# Incubadora_huevos.net
KiCad netlist of a schematic drawn in EAGLE
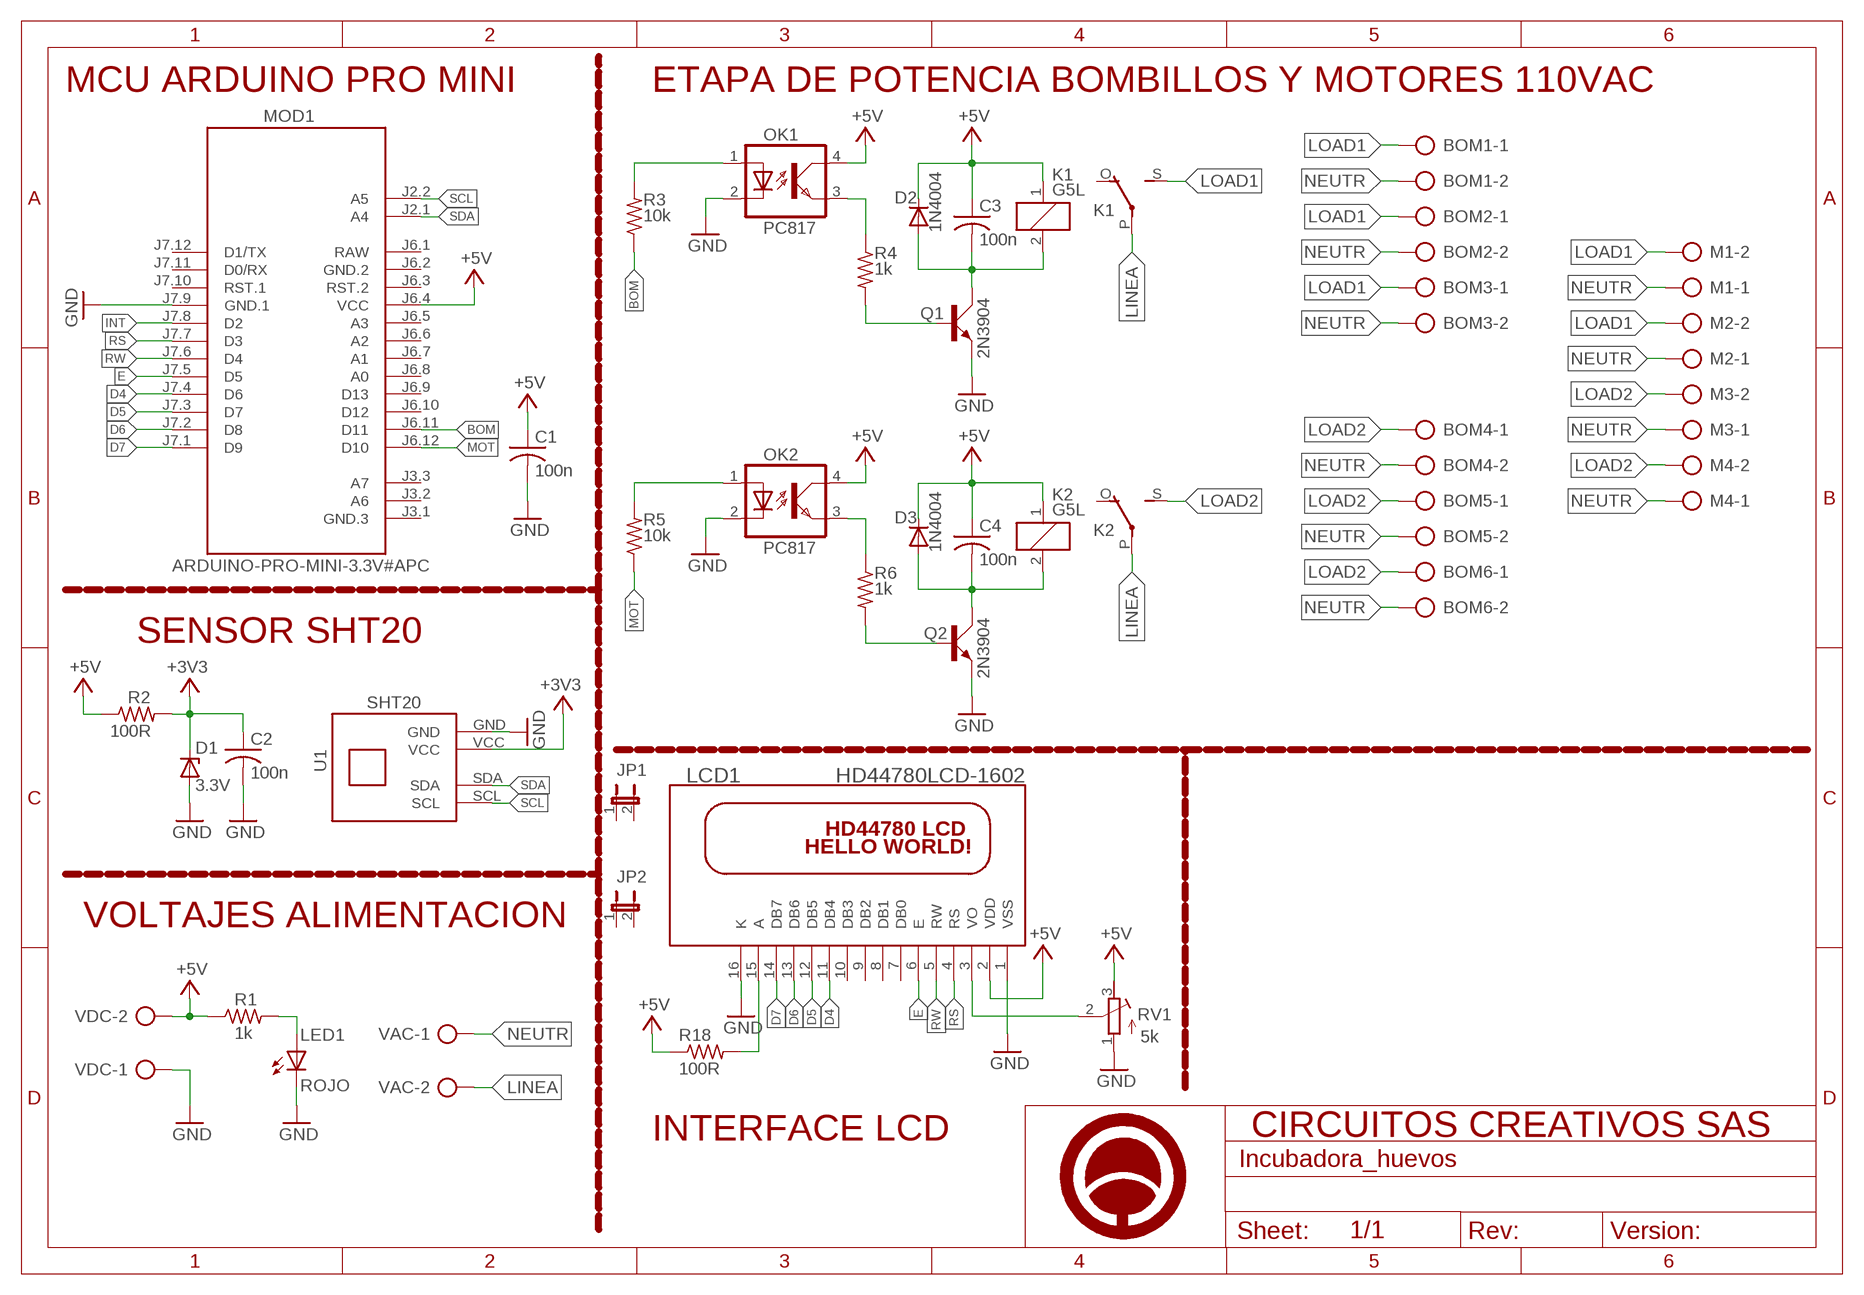
[diagram p0: schematic, sheet 1]

(export (version "E")
  (design (tool "Eeschema 10.0.6"))
  (components
    (comp (ref "BOM1")
      (value "AK500/2")
      (footprint "eagle-import:AK500_2")
      (libsource (lib "eagle-import") (part "AK500/2"))
    )
    (comp (ref "BOM2")
      (value "AK500/2")
      (footprint "eagle-import:AK500_2")
      (libsource (lib "eagle-import") (part "AK500/2"))
    )
    (comp (ref "BOM3")
      (value "AK500/2")
      (footprint "eagle-import:AK500_2")
      (libsource (lib "eagle-import") (part "AK500/2"))
    )
    (comp (ref "BOM4")
      (value "AK500/2")
      (footprint "eagle-import:AK500_2")
      (libsource (lib "eagle-import") (part "AK500/2"))
    )
    (comp (ref "BOM5")
      (value "AK500/2")
      (footprint "eagle-import:AK500_2")
      (libsource (lib "eagle-import") (part "AK500/2"))
    )
    (comp (ref "BOM6")
      (value "AK500/2")
      (footprint "eagle-import:AK500_2")
      (libsource (lib "eagle-import") (part "AK500/2"))
    )
    (comp (ref "C1")
      (value "100n")
      (footprint "eagle-import:C025-025X050")
      (libsource (lib "eagle-import") (part "C-US025-025X050"))
    )
    (comp (ref "C2")
      (value "100n")
      (footprint "eagle-import:C025-025X050")
      (libsource (lib "eagle-import") (part "C-US025-025X050"))
    )
    (comp (ref "C3")
      (value "100n")
      (footprint "eagle-import:C025-025X050")
      (libsource (lib "eagle-import") (part "C-US025-025X050"))
    )
    (comp (ref "C4")
      (value "100n")
      (footprint "eagle-import:C025-025X050")
      (libsource (lib "eagle-import") (part "C-US025-025X050"))
    )
    (comp (ref "D1")
      (value "3.3V")
      (footprint "eagle-import:DO41Z10")
      (libsource (lib "eagle-import") (part "ZENER-DIODEDO41Z10"))
    )
    (comp (ref "D2")
      (value "1N4004")
      (footprint "eagle-import:DO41-10")
      (libsource (lib "eagle-import") (part "1N4004"))
    )
    (comp (ref "D3")
      (value "1N4004")
      (footprint "eagle-import:DO41-10")
      (libsource (lib "eagle-import") (part "1N4004"))
    )
    (comp (ref "JP1")
      (value "JP1E")
      (footprint "eagle-import:JP1")
      (libsource (lib "eagle-import") (part "JP1E"))
    )
    (comp (ref "JP2")
      (value "JP1E")
      (footprint "eagle-import:JP1")
      (libsource (lib "eagle-import") (part "JP1E"))
    )
    (comp (ref "K1")
      (value "G5L")
      (footprint "eagle-import:G5LE")
      (libsource (lib "eagle-import") (part "G5L"))
    )
    (comp (ref "K2")
      (value "G5L")
      (footprint "eagle-import:G5LE")
      (libsource (lib "eagle-import") (part "G5L"))
    )
    (comp (ref "LCD1")
      (value "HD44780LCD-1602")
      (footprint "eagle-import:LCD1602")
      (libsource (lib "eagle-import") (part "HD44780LCD-1602"))
    )
    (comp (ref "LED1")
      (value "ROJO")
      (footprint "eagle-import:LED3MM")
      (libsource (lib "eagle-import") (part "LED3MM"))
    )
    (comp (ref "M1")
      (value "AK500/2")
      (footprint "eagle-import:AK500_2")
      (libsource (lib "eagle-import") (part "AK500/2"))
    )
    (comp (ref "M2")
      (value "AK500/2")
      (footprint "eagle-import:AK500_2")
      (libsource (lib "eagle-import") (part "AK500/2"))
    )
    (comp (ref "M3")
      (value "AK500/2")
      (footprint "eagle-import:AK500_2")
      (libsource (lib "eagle-import") (part "AK500/2"))
    )
    (comp (ref "M4")
      (value "AK500/2")
      (footprint "eagle-import:AK500_2")
      (libsource (lib "eagle-import") (part "AK500/2"))
    )
    (comp (ref "MOD1")
      (value "ARDUINO-PRO-MINI-3.3V#APC")
      (footprint "eagle-import:ARDUINO-PRO-MINI#APC")
      (libsource (lib "eagle-import") (part "ARDUINO-PRO-MINI-#APC3.3V"))
    )
    (comp (ref "OK1")
      (value "PC817")
      (footprint "eagle-import:DIL04")
      (fields (field (name "MPN") "PC817X4J000F"))
      (libsource (lib "eagle-import") (part "PC817"))
    )
    (comp (ref "OK2")
      (value "PC817")
      (footprint "eagle-import:DIL04")
      (fields (field (name "MPN") "PC817X4J000F"))
      (libsource (lib "eagle-import") (part "PC817"))
    )
    (comp (ref "Q1")
      (value "2N3904")
      (footprint "eagle-import:TO92D")
      (libsource (lib "eagle-import") (part "2N3904"))
    )
    (comp (ref "Q2")
      (value "2N3904")
      (footprint "eagle-import:TO92D")
      (libsource (lib "eagle-import") (part "2N3904"))
    )
    (comp (ref "R1")
      (value "1k")
      (footprint "eagle-import:0204_7")
      (libsource (lib "eagle-import") (part "R-US_0204/7"))
    )
    (comp (ref "R2")
      (value "100R")
      (footprint "eagle-import:0204_7")
      (libsource (lib "eagle-import") (part "R-US_0204/7"))
    )
    (comp (ref "R3")
      (value "10k")
      (footprint "eagle-import:0204_7")
      (libsource (lib "eagle-import") (part "R-US_0204/7"))
    )
    (comp (ref "R4")
      (value "1k")
      (footprint "eagle-import:0204_7")
      (libsource (lib "eagle-import") (part "R-US_0204/7"))
    )
    (comp (ref "R5")
      (value "10k")
      (footprint "eagle-import:0204_7")
      (libsource (lib "eagle-import") (part "R-US_0204/7"))
    )
    (comp (ref "R6")
      (value "1k")
      (footprint "eagle-import:0204_7")
      (libsource (lib "eagle-import") (part "R-US_0204/7"))
    )
    (comp (ref "R18")
      (value "100R")
      (footprint "eagle-import:0204_7")
      (libsource (lib "eagle-import") (part "R-US_0204/7"))
    )
    (comp (ref "RV1")
      (value "5k")
      (footprint "eagle-import:RTRIM3296W")
      (libsource (lib "eagle-import") (part "R-TRIMM3296W"))
    )
    (comp (ref "U$1")
      (value "A4_HORIZONTAL")
      (footprint "eagle-import:LOGO")
      (libsource (lib "eagle-import") (part "A4_HORIZONTAL"))
    )
    (comp (ref "U1")
      (value "SHT20")
      (footprint "eagle-import:SHT20")
      (libsource (lib "eagle-import") (part "SHT20"))
    )
    (comp (ref "VAC")
      (value "AK500/2")
      (footprint "eagle-import:AK500_2")
      (libsource (lib "eagle-import") (part "AK500/2"))
    )
    (comp (ref "VDC")
      (value "AK500/2")
      (footprint "eagle-import:AK500_2")
      (libsource (lib "eagle-import") (part "AK500/2"))
    )
  )
  (nets
    (net (code "1") (name "+3V3") (class "Default")
      (node (ref "C2") (pin "1") (pinfunction "1_1") (pintype "passive"))
      (node (ref "D1") (pin "C") (pinfunction "C_C") (pintype "passive"))
      (node (ref "R2") (pin "2") (pinfunction "2_2") (pintype "passive"))
      (node (ref "U1") (pin "VCC") (pinfunction "VCC_VCC") (pintype "power_in"))
    )
    (net (code "2") (name "+5V") (class "Default")
      (node (ref "C1") (pin "1") (pinfunction "1_1") (pintype "passive"))
      (node (ref "C3") (pin "1") (pinfunction "1_1") (pintype "passive"))
      (node (ref "C4") (pin "1") (pinfunction "1_1") (pintype "passive"))
      (node (ref "D2") (pin "C") (pinfunction "C_C") (pintype "passive"))
      (node (ref "D3") (pin "C") (pinfunction "C_C") (pintype "passive"))
      (node (ref "K1") (pin "1") (pinfunction "1_1") (pintype "passive"))
      (node (ref "K2") (pin "1") (pinfunction "1_1") (pintype "passive"))
      (node (ref "LCD1") (pin "2") (pinfunction "VDD_2") (pintype "power_in"))
      (node (ref "MOD1") (pin "J6.4") (pinfunction "VCC_J6.4") (pintype "power_in"))
      (node (ref "OK1") (pin "4") (pinfunction "COL_4") (pintype "passive"))
      (node (ref "OK2") (pin "4") (pinfunction "COL_4") (pintype "passive"))
      (node (ref "R1") (pin "1") (pinfunction "1_1") (pintype "passive"))
      (node (ref "R18") (pin "1") (pinfunction "1_1") (pintype "passive"))
      (node (ref "R2") (pin "1") (pinfunction "1_1") (pintype "passive"))
      (node (ref "RV1") (pin "3") (pinfunction "E_3") (pintype "passive"))
      (node (ref "VDC") (pin "2") (pinfunction "KL_2") (pintype "passive"))
    )
    (net (code "3") (name "/GND.2") (class "Default")
      (node (ref "MOD1") (pin "J6.2") (pinfunction "GND.2_J6.2") (pintype "power_in"))
    )
    (net (code "4") (name "/RAW") (class "Default")
      (node (ref "MOD1") (pin "J6.1") (pinfunction "RAW_J6.1") (pintype "power_in"))
    )
    (net (code "5") (name "BOM") (class "Default")
      (node (ref "MOD1") (pin "J6.11") (pinfunction "D11_J6.11") (pintype "bidirectional"))
      (node (ref "R3") (pin "1") (pinfunction "1_1") (pintype "passive"))
    )
    (net (code "6") (name "D4") (class "Default")
      (node (ref "LCD1") (pin "11") (pinfunction "DB4_11") (pintype "bidirectional"))
      (node (ref "MOD1") (pin "J7.4") (pinfunction "D6_J7.4") (pintype "bidirectional"))
    )
    (net (code "7") (name "D5") (class "Default")
      (node (ref "LCD1") (pin "12") (pinfunction "DB5_12") (pintype "bidirectional"))
      (node (ref "MOD1") (pin "J7.3") (pinfunction "D7_J7.3") (pintype "bidirectional"))
    )
    (net (code "8") (name "D6") (class "Default")
      (node (ref "LCD1") (pin "13") (pinfunction "DB6_13") (pintype "bidirectional"))
      (node (ref "MOD1") (pin "J7.2") (pinfunction "D8_J7.2") (pintype "bidirectional"))
    )
    (net (code "9") (name "D7") (class "Default")
      (node (ref "LCD1") (pin "14") (pinfunction "DB7_14") (pintype "bidirectional"))
      (node (ref "MOD1") (pin "J7.1") (pinfunction "D9_J7.1") (pintype "bidirectional"))
    )
    (net (code "10") (name "E") (class "Default")
      (node (ref "LCD1") (pin "6") (pinfunction "E_6") (pintype "input"))
      (node (ref "MOD1") (pin "J7.5") (pinfunction "D5_J7.5") (pintype "bidirectional"))
    )
    (net (code "11") (name "GND") (class "Default")
      (node (ref "C1") (pin "2") (pinfunction "2_2") (pintype "passive"))
      (node (ref "C2") (pin "2") (pinfunction "2_2") (pintype "passive"))
      (node (ref "D1") (pin "A") (pinfunction "A_A") (pintype "passive"))
      (node (ref "LCD1") (pin "1") (pinfunction "VSS_1") (pintype "power_in"))
      (node (ref "LCD1") (pin "16") (pinfunction "K_16") (pintype "input"))
      (node (ref "LED1") (pin "K") (pinfunction "C_K") (pintype "passive"))
      (node (ref "MOD1") (pin "J7.9") (pinfunction "GND.1_J7.9") (pintype "power_in"))
      (node (ref "OK1") (pin "2") (pinfunction "C_2") (pintype "passive"))
      (node (ref "OK2") (pin "2") (pinfunction "C_2") (pintype "passive"))
      (node (ref "Q1") (pin "E") (pinfunction "E_E") (pintype "passive"))
      (node (ref "Q2") (pin "E") (pinfunction "E_E") (pintype "passive"))
      (node (ref "RV1") (pin "1") (pinfunction "A_1") (pintype "passive"))
      (node (ref "U1") (pin "GND") (pinfunction "GND_GND") (pintype "power_in"))
      (node (ref "VDC") (pin "1") (pinfunction "KL_1") (pintype "passive"))
    )
    (net (code "12") (name "INT") (class "Default")
      (node (ref "MOD1") (pin "J7.8") (pinfunction "D2_J7.8") (pintype "bidirectional"))
    )
    (net (code "13") (name "LINEA") (class "Default")
      (node (ref "K1") (pin "P") (pinfunction "P_P") (pintype "passive"))
      (node (ref "K2") (pin "P") (pinfunction "P_P") (pintype "passive"))
      (node (ref "VAC") (pin "2") (pinfunction "KL_2") (pintype "passive"))
    )
    (net (code "14") (name "LOAD1") (class "Default")
      (node (ref "BOM1") (pin "1") (pinfunction "KL_1") (pintype "passive"))
      (node (ref "BOM2") (pin "1") (pinfunction "KL_1") (pintype "passive"))
      (node (ref "BOM3") (pin "1") (pinfunction "KL_1") (pintype "passive"))
      (node (ref "K1") (pin "S") (pinfunction "S_S") (pintype "passive"))
      (node (ref "M1") (pin "2") (pinfunction "KL_2") (pintype "passive"))
      (node (ref "M2") (pin "2") (pinfunction "KL_2") (pintype "passive"))
    )
    (net (code "15") (name "LOAD2") (class "Default")
      (node (ref "BOM4") (pin "1") (pinfunction "KL_1") (pintype "passive"))
      (node (ref "BOM5") (pin "1") (pinfunction "KL_1") (pintype "passive"))
      (node (ref "BOM6") (pin "1") (pinfunction "KL_1") (pintype "passive"))
      (node (ref "K2") (pin "S") (pinfunction "S_S") (pintype "passive"))
      (node (ref "M3") (pin "2") (pinfunction "KL_2") (pintype "passive"))
      (node (ref "M4") (pin "2") (pinfunction "KL_2") (pintype "passive"))
    )
    (net (code "16") (name "MOT") (class "Default")
      (node (ref "MOD1") (pin "J6.12") (pinfunction "D10_J6.12") (pintype "bidirectional"))
      (node (ref "R5") (pin "1") (pinfunction "1_1") (pintype "passive"))
    )
    (net (code "17") (name "NEUTR") (class "Default")
      (node (ref "BOM1") (pin "2") (pinfunction "KL_2") (pintype "passive"))
      (node (ref "BOM2") (pin "2") (pinfunction "KL_2") (pintype "passive"))
      (node (ref "BOM3") (pin "2") (pinfunction "KL_2") (pintype "passive"))
      (node (ref "BOM4") (pin "2") (pinfunction "KL_2") (pintype "passive"))
      (node (ref "BOM5") (pin "2") (pinfunction "KL_2") (pintype "passive"))
      (node (ref "BOM6") (pin "2") (pinfunction "KL_2") (pintype "passive"))
      (node (ref "M1") (pin "1") (pinfunction "KL_1") (pintype "passive"))
      (node (ref "M2") (pin "1") (pinfunction "KL_1") (pintype "passive"))
      (node (ref "M3") (pin "1") (pinfunction "KL_1") (pintype "passive"))
      (node (ref "M4") (pin "1") (pinfunction "KL_1") (pintype "passive"))
      (node (ref "VAC") (pin "1") (pinfunction "KL_1") (pintype "passive"))
    )
    (net (code "18") (name "Net-(C3-Pad2)") (class "Default")
      (node (ref "C3") (pin "2") (pinfunction "2_2") (pintype "passive"))
      (node (ref "D2") (pin "A") (pinfunction "A_A") (pintype "passive"))
      (node (ref "K1") (pin "2") (pinfunction "2_2") (pintype "passive"))
      (node (ref "Q1") (pin "C") (pinfunction "C_C") (pintype "passive"))
    )
    (net (code "19") (name "Net-(C4-Pad2)") (class "Default")
      (node (ref "C4") (pin "2") (pinfunction "2_2") (pintype "passive"))
      (node (ref "D3") (pin "A") (pinfunction "A_A") (pintype "passive"))
      (node (ref "K2") (pin "2") (pinfunction "2_2") (pintype "passive"))
      (node (ref "Q2") (pin "C") (pinfunction "C_C") (pintype "passive"))
    )
    (net (code "20") (name "Net-(LCD1-A)") (class "Default")
      (node (ref "LCD1") (pin "15") (pinfunction "A_15") (pintype "input"))
      (node (ref "R18") (pin "2") (pinfunction "2_2") (pintype "passive"))
    )
    (net (code "21") (name "Net-(LCD1-VO)") (class "Default")
      (node (ref "LCD1") (pin "3") (pinfunction "VO_3") (pintype "input"))
      (node (ref "RV1") (pin "2") (pinfunction "S_2") (pintype "passive"))
    )
    (net (code "22") (name "Net-(LED1-PadA)") (class "Default")
      (node (ref "LED1") (pin "A") (pinfunction "A_A") (pintype "passive"))
      (node (ref "R1") (pin "2") (pinfunction "2_2") (pintype "passive"))
    )
    (net (code "23") (name "Net-(OK1-A)") (class "Default")
      (node (ref "OK1") (pin "1") (pinfunction "A_1") (pintype "passive"))
      (node (ref "R3") (pin "2") (pinfunction "2_2") (pintype "passive"))
    )
    (net (code "24") (name "Net-(OK1-EMIT)") (class "Default")
      (node (ref "OK1") (pin "3") (pinfunction "EMIT_3") (pintype "passive"))
      (node (ref "R4") (pin "1") (pinfunction "1_1") (pintype "passive"))
    )
    (net (code "25") (name "Net-(OK2-A)") (class "Default")
      (node (ref "OK2") (pin "1") (pinfunction "A_1") (pintype "passive"))
      (node (ref "R5") (pin "2") (pinfunction "2_2") (pintype "passive"))
    )
    (net (code "26") (name "Net-(OK2-EMIT)") (class "Default")
      (node (ref "OK2") (pin "3") (pinfunction "EMIT_3") (pintype "passive"))
      (node (ref "R6") (pin "1") (pinfunction "1_1") (pintype "passive"))
    )
    (net (code "27") (name "Net-(Q1-PadB)") (class "Default")
      (node (ref "Q1") (pin "B") (pinfunction "B_B") (pintype "passive"))
      (node (ref "R4") (pin "2") (pinfunction "2_2") (pintype "passive"))
    )
    (net (code "28") (name "Net-(Q2-PadB)") (class "Default")
      (node (ref "Q2") (pin "B") (pinfunction "B_B") (pintype "passive"))
      (node (ref "R6") (pin "2") (pinfunction "2_2") (pintype "passive"))
    )
    (net (code "29") (name "RS") (class "Default")
      (node (ref "LCD1") (pin "4") (pinfunction "RS_4") (pintype "input"))
      (node (ref "MOD1") (pin "J7.7") (pinfunction "D3_J7.7") (pintype "bidirectional"))
    )
    (net (code "30") (name "RW") (class "Default")
      (node (ref "LCD1") (pin "5") (pinfunction "RW_5") (pintype "input"))
      (node (ref "MOD1") (pin "J7.6") (pinfunction "D4_J7.6") (pintype "bidirectional"))
    )
    (net (code "31") (name "SCL") (class "Default")
      (node (ref "MOD1") (pin "J2.2") (pinfunction "A5_J2.2") (pintype "bidirectional"))
      (node (ref "U1") (pin "SCL") (pinfunction "SCL_SCL") (pintype "bidirectional"))
    )
    (net (code "32") (name "SDA") (class "Default")
      (node (ref "MOD1") (pin "J2.1") (pinfunction "A4_J2.1") (pintype "bidirectional"))
      (node (ref "U1") (pin "SDA") (pinfunction "SDA_SDA") (pintype "bidirectional"))
    )
    (net (code "33") (name "unconnected-(JP1-Pad1)") (class "Default")
      (node (ref "JP1") (pin "1") (pinfunction "1_1") (pintype "passive"))
    )
    (net (code "34") (name "unconnected-(JP1-Pad2)") (class "Default")
      (node (ref "JP1") (pin "2") (pinfunction "2_2") (pintype "passive"))
    )
    (net (code "35") (name "unconnected-(JP2-Pad1)") (class "Default")
      (node (ref "JP2") (pin "1") (pinfunction "1_1") (pintype "passive"))
    )
    (net (code "36") (name "unconnected-(JP2-Pad2)") (class "Default")
      (node (ref "JP2") (pin "2") (pinfunction "2_2") (pintype "passive"))
    )
    (net (code "37") (name "unconnected-(K1-PadO)") (class "Default")
      (node (ref "K1") (pin "O") (pinfunction "O_O") (pintype "passive"))
    )
    (net (code "38") (name "unconnected-(K2-PadO)") (class "Default")
      (node (ref "K2") (pin "O") (pinfunction "O_O") (pintype "passive"))
    )
    (net (code "39") (name "unconnected-(LCD1-DB0-Pad7)") (class "Default")
      (node (ref "LCD1") (pin "7") (pinfunction "DB0_7") (pintype "bidirectional"))
    )
    (net (code "40") (name "unconnected-(LCD1-DB1-Pad8)") (class "Default")
      (node (ref "LCD1") (pin "8") (pinfunction "DB1_8") (pintype "bidirectional"))
    )
    (net (code "41") (name "unconnected-(LCD1-DB2-Pad9)") (class "Default")
      (node (ref "LCD1") (pin "9") (pinfunction "DB2_9") (pintype "bidirectional"))
    )
    (net (code "42") (name "unconnected-(LCD1-DB3-Pad10)") (class "Default")
      (node (ref "LCD1") (pin "10") (pinfunction "DB3_10") (pintype "bidirectional"))
    )
    (net (code "43") (name "unconnected-(MOD1-A0-PadJ6.8)") (class "Default")
      (node (ref "MOD1") (pin "J6.8") (pinfunction "A0_J6.8") (pintype "bidirectional"))
    )
    (net (code "44") (name "unconnected-(MOD1-A1-PadJ6.7)") (class "Default")
      (node (ref "MOD1") (pin "J6.7") (pinfunction "A1_J6.7") (pintype "bidirectional"))
    )
    (net (code "45") (name "unconnected-(MOD1-A2-PadJ6.6)") (class "Default")
      (node (ref "MOD1") (pin "J6.6") (pinfunction "A2_J6.6") (pintype "bidirectional"))
    )
    (net (code "46") (name "unconnected-(MOD1-A3-PadJ6.5)") (class "Default")
      (node (ref "MOD1") (pin "J6.5") (pinfunction "A3_J6.5") (pintype "bidirectional"))
    )
    (net (code "47") (name "unconnected-(MOD1-A6-PadJ3.2)") (class "Default")
      (node (ref "MOD1") (pin "J3.2") (pinfunction "A6_J3.2") (pintype "bidirectional"))
    )
    (net (code "48") (name "unconnected-(MOD1-A7-PadJ3.3)") (class "Default")
      (node (ref "MOD1") (pin "J3.3") (pinfunction "A7_J3.3") (pintype "bidirectional"))
    )
    (net (code "49") (name "unconnected-(MOD1-D0{slash}RX-PadJ7.11)") (class "Default")
      (node (ref "MOD1") (pin "J7.11") (pinfunction "D0/RX_J7.11") (pintype "bidirectional"))
    )
    (net (code "50") (name "unconnected-(MOD1-D1{slash}TX-PadJ7.12)") (class "Default")
      (node (ref "MOD1") (pin "J7.12") (pinfunction "D1/TX_J7.12") (pintype "bidirectional"))
    )
    (net (code "51") (name "unconnected-(MOD1-D12-PadJ6.10)") (class "Default")
      (node (ref "MOD1") (pin "J6.10") (pinfunction "D12_J6.10") (pintype "bidirectional"))
    )
    (net (code "52") (name "unconnected-(MOD1-D13-PadJ6.9)") (class "Default")
      (node (ref "MOD1") (pin "J6.9") (pinfunction "D13_J6.9") (pintype "bidirectional"))
    )
    (net (code "53") (name "unconnected-(MOD1-GND.3-PadJ3.1)") (class "Default")
      (node (ref "MOD1") (pin "J3.1") (pinfunction "GND.3_J3.1") (pintype "bidirectional"))
    )
    (net (code "54") (name "unconnected-(MOD1-RST.1-PadJ7.10)") (class "Default")
      (node (ref "MOD1") (pin "J7.10") (pinfunction "RST.1_J7.10") (pintype "bidirectional"))
    )
    (net (code "55") (name "unconnected-(MOD1-RST.2-PadJ6.3)") (class "Default")
      (node (ref "MOD1") (pin "J6.3") (pinfunction "RST.2_J6.3") (pintype "bidirectional"))
    )
  )
)
